# I2CADC.net
KiCad netlist of a schematic drawn in Altium Designer
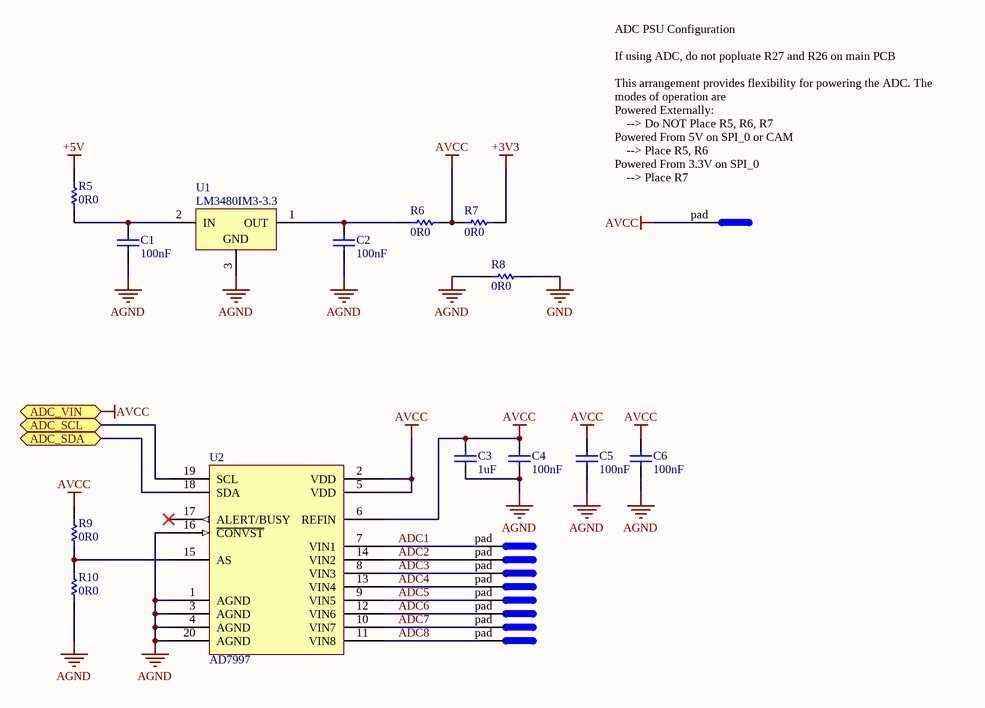
[diagram p0: I2CADC.SchDoc]

(export (version "E")
  (design (tool "Eeschema 10.0.6"))
  (components
    (comp (ref "A+")
      (value "~")
      (footprint "PAD_ROUND")
      (description "Pad")
      (libsource (lib "GRC sch library") (part "JP_pad"))
    )
    (comp (ref "A1")
      (value "~")
      (footprint "PAD_ROUND")
      (description "Pad")
      (libsource (lib "GRC sch library") (part "JP_pad"))
    )
    (comp (ref "A2")
      (value "~")
      (footprint "PAD_ROUND")
      (description "Pad")
      (libsource (lib "GRC sch library") (part "JP_pad"))
    )
    (comp (ref "A3")
      (value "~")
      (footprint "PAD_ROUND")
      (description "Pad")
      (libsource (lib "GRC sch library") (part "JP_pad"))
    )
    (comp (ref "A4")
      (value "~")
      (footprint "PAD_ROUND")
      (description "Pad")
      (libsource (lib "GRC sch library") (part "JP_pad"))
    )
    (comp (ref "A5")
      (value "~")
      (footprint "PAD_ROUND")
      (description "Pad")
      (libsource (lib "GRC sch library") (part "JP_pad"))
    )
    (comp (ref "A6")
      (value "~")
      (footprint "PAD_ROUND")
      (description "Pad")
      (libsource (lib "GRC sch library") (part "JP_pad"))
    )
    (comp (ref "A7")
      (value "~")
      (footprint "PAD_ROUND")
      (description "Pad")
      (libsource (lib "GRC sch library") (part "JP_pad"))
    )
    (comp (ref "A8")
      (value "~")
      (footprint "PAD_ROUND")
      (description "Pad")
      (libsource (lib "GRC sch library") (part "JP_pad"))
    )
    (comp (ref "C1")
      (value "100nF")
      (footprint "GRC PCB library:0603")
      (description "CAP CER .10UF 50V X5R 0603")
      (fields (field (name "MANUFACTURER") "Taiyo Yuden"))
      (libsource (lib "GRC sch library") (part "CP_100nF 0603"))
    )
    (comp (ref "C2")
      (value "100nF")
      (footprint "GRC PCB library:0603")
      (description "CAP CER .10UF 50V X5R 0603")
      (fields (field (name "MANUFACTURER") "Taiyo Yuden"))
      (libsource (lib "GRC sch library") (part "CP_100nF 0603"))
    )
    (comp (ref "C3")
      (value "1uF")
      (footprint "GRC PCB library:0603")
      (description "CAP CER 1.0UF 50V X5S 0603")
      (fields (field (name "MANUFACTURER") "Taiyo Yuden"))
      (libsource (lib "GRC sch library") (part "CP_1uF 0603"))
    )
    (comp (ref "C4")
      (value "100nF")
      (footprint "GRC PCB library:0603")
      (description "CAP CER .10UF 50V X5R 0603")
      (fields (field (name "MANUFACTURER") "Taiyo Yuden"))
      (libsource (lib "GRC sch library") (part "CP_100nF 0603"))
    )
    (comp (ref "C5")
      (value "100nF")
      (footprint "GRC PCB library:0603")
      (description "CAP CER .10UF 50V X5R 0603")
      (fields (field (name "MANUFACTURER") "Taiyo Yuden"))
      (libsource (lib "GRC sch library") (part "CP_100nF 0603"))
    )
    (comp (ref "C6")
      (value "100nF")
      (footprint "GRC PCB library:0603")
      (description "CAP CER .10UF 50V X5R 0603")
      (fields (field (name "MANUFACTURER") "Taiyo Yuden"))
      (libsource (lib "GRC sch library") (part "CP_100nF 0603"))
    )
    (comp (ref "R5")
      (value "0R0")
      (footprint "0805")
      (description "RES 0.0 OHM 1/10W 5% 1206 SMD")
      (fields (field (name "MANUFACTURER") "Rohm"))
      (libsource (lib "GRC sch library") (part "RS_0R0 0603"))
    )
    (comp (ref "R6")
      (value "0R0")
      (footprint "0805")
      (description "RES 0.0 OHM 1/10W 5% 1206 SMD")
      (fields (field (name "MANUFACTURER") "Rohm"))
      (libsource (lib "GRC sch library") (part "RS_0R0 0603"))
    )
    (comp (ref "R7")
      (value "0R0")
      (footprint "0805")
      (description "RES 0.0 OHM 1/10W 5% 1206 SMD")
      (fields (field (name "MANUFACTURER") "Rohm"))
      (libsource (lib "GRC sch library") (part "RS_0R0 0603"))
    )
    (comp (ref "R8")
      (value "0R0")
      (footprint "0805")
      (description "RES 0.0 OHM 1/10W 5% 1206 SMD")
      (fields (field (name "MANUFACTURER") "Rohm"))
      (libsource (lib "GRC sch library") (part "RS_0R0 0603"))
    )
    (comp (ref "R9")
      (value "0R0")
      (footprint "0805")
      (description "RES 0.0 OHM 1/10W 5% 0603 SMD")
      (fields (field (name "MANUFACTURER") "Rohm"))
      (libsource (lib "GRC sch library") (part "RS_0R0 0603"))
    )
    (comp (ref "R10")
      (value "0R0")
      (footprint "0805")
      (description "RES 0.0 OHM 1/10W 5% 0603 SMD")
      (fields (field (name "MANUFACTURER") "Rohm"))
      (libsource (lib "GRC sch library") (part "RS_0R0 0603"))
    )
    (comp (ref "U1")
      (value "LM3480IM3-3.3")
      (footprint "MF03A_N")
      (description "100 mA, SOT-23, Quasi Low-Dropout Linear Voltage Regulator")
      (fields
        (field (name "MANUFACTURER") "National Semiconductor")
        (field (name "DIGIKEYPARTNUMBER") "LM3480IM3-3.3CT-ND")
        (field (name "PUBLISHER") "Altium Limited")
      )
      (libsource (lib "NSC LDO") (part "LM3480IM3-3.3"))
    )
    (comp (ref "U2")
      (value "AD7997")
      (footprint "TSOP65P640-20AM")
      (description "10-bit 8 channel ADC")
      (libsource (lib "GRC sch library") (part "IC_AD7997"))
    )
  )
  (nets
    (net (code "1") (name "+3V3") (class "Default")
      (node (ref "R7") (pin "1") (pinfunction "1_1") (pintype "passive"))
    )
    (net (code "2") (name "+5V") (class "Default")
      (node (ref "R5") (pin "2") (pinfunction "2_2") (pintype "passive"))
    )
    (net (code "3") (name "/ADC1") (class "Default")
      (node (ref "A1") (pin "pad") (pintype "passive"))
      (node (ref "U2") (pin "7") (pinfunction "VIN1_7") (pintype "passive"))
    )
    (net (code "4") (name "/ADC2") (class "Default")
      (node (ref "A2") (pin "pad") (pintype "passive"))
      (node (ref "U2") (pin "14") (pinfunction "VIN2_14") (pintype "passive"))
    )
    (net (code "5") (name "/ADC3") (class "Default")
      (node (ref "A3") (pin "pad") (pintype "passive"))
      (node (ref "U2") (pin "8") (pinfunction "VIN3_8") (pintype "passive"))
    )
    (net (code "6") (name "/ADC4") (class "Default")
      (node (ref "A4") (pin "pad") (pintype "passive"))
      (node (ref "U2") (pin "13") (pinfunction "VIN4_13") (pintype "passive"))
    )
    (net (code "7") (name "/ADC5") (class "Default")
      (node (ref "A5") (pin "pad") (pintype "passive"))
      (node (ref "U2") (pin "9") (pinfunction "VIN5_9") (pintype "passive"))
    )
    (net (code "8") (name "/ADC6") (class "Default")
      (node (ref "A6") (pin "pad") (pintype "passive"))
      (node (ref "U2") (pin "12") (pinfunction "VIN6_12") (pintype "passive"))
    )
    (net (code "9") (name "/ADC7") (class "Default")
      (node (ref "A7") (pin "pad") (pintype "passive"))
      (node (ref "U2") (pin "10") (pinfunction "VIN7_10") (pintype "passive"))
    )
    (net (code "10") (name "/ADC8") (class "Default")
      (node (ref "A8") (pin "pad") (pintype "passive"))
      (node (ref "U2") (pin "11") (pinfunction "VIN8_11") (pintype "passive"))
    )
    (net (code "11") (name "/ADC_SCL") (class "Default")
      (node (ref "U2") (pin "19") (pinfunction "SCL_19") (pintype "passive"))
    )
    (net (code "12") (name "/ADC_SDA") (class "Default")
      (node (ref "U2") (pin "18") (pinfunction "SDA_18") (pintype "passive"))
    )
    (net (code "13") (name "AGND") (class "Default")
      (node (ref "C1") (pin "1") (pinfunction "1_1") (pintype "passive"))
      (node (ref "C2") (pin "1") (pinfunction "1_1") (pintype "passive"))
      (node (ref "C3") (pin "1") (pinfunction "1_1") (pintype "passive"))
      (node (ref "C4") (pin "1") (pinfunction "1_1") (pintype "passive"))
      (node (ref "C5") (pin "1") (pinfunction "1_1") (pintype "passive"))
      (node (ref "C6") (pin "1") (pinfunction "1_1") (pintype "passive"))
      (node (ref "R10") (pin "2") (pinfunction "2_2") (pintype "passive"))
      (node (ref "R8") (pin "1") (pinfunction "1_1") (pintype "passive"))
      (node (ref "U1") (pin "3") (pinfunction "GND_3") (pintype "power_in"))
      (node (ref "U2") (pin "1") (pinfunction "AGND_1") (pintype "power_in"))
      (node (ref "U2") (pin "16") (pinfunction "~{CONVST}_16") (pintype "input"))
      (node (ref "U2") (pin "20") (pinfunction "AGND_20") (pintype "power_in"))
      (node (ref "U2") (pin "3") (pinfunction "AGND_3") (pintype "power_in"))
      (node (ref "U2") (pin "4") (pinfunction "AGND_4") (pintype "power_in"))
    )
    (net (code "14") (name "AVCC") (class "Default")
      (node (ref "A+") (pin "pad") (pintype "passive"))
      (node (ref "C3") (pin "2") (pinfunction "2_2") (pintype "passive"))
      (node (ref "C4") (pin "2") (pinfunction "2_2") (pintype "passive"))
      (node (ref "C5") (pin "2") (pinfunction "2_2") (pintype "passive"))
      (node (ref "C6") (pin "2") (pinfunction "2_2") (pintype "passive"))
      (node (ref "R6") (pin "1") (pinfunction "1_1") (pintype "passive"))
      (node (ref "R7") (pin "2") (pinfunction "2_2") (pintype "passive"))
      (node (ref "R9") (pin "2") (pinfunction "2_2") (pintype "passive"))
      (node (ref "U2") (pin "2") (pinfunction "VDD_2") (pintype "power_in"))
      (node (ref "U2") (pin "5") (pinfunction "VDD_5") (pintype "power_in"))
      (node (ref "U2") (pin "6") (pinfunction "REFIN_6") (pintype "passive"))
    )
    (net (code "15") (name "GND") (class "Default")
      (node (ref "R8") (pin "2") (pinfunction "2_2") (pintype "passive"))
    )
    (net (code "16") (name "Net-(U1-IN)") (class "Default")
      (node (ref "C1") (pin "2") (pinfunction "2_2") (pintype "passive"))
      (node (ref "R5") (pin "1") (pinfunction "1_1") (pintype "passive"))
      (node (ref "U1") (pin "2") (pinfunction "IN_2") (pintype "power_in"))
    )
    (net (code "17") (name "Net-(U1-OUT)") (class "Default")
      (node (ref "C2") (pin "2") (pinfunction "2_2") (pintype "passive"))
      (node (ref "R6") (pin "2") (pinfunction "2_2") (pintype "passive"))
      (node (ref "U1") (pin "1") (pinfunction "OUT_1") (pintype "power_in"))
    )
    (net (code "18") (name "Net-(U2-AS)") (class "Default")
      (node (ref "R10") (pin "1") (pinfunction "1_1") (pintype "passive"))
      (node (ref "R9") (pin "1") (pinfunction "1_1") (pintype "passive"))
      (node (ref "U2") (pin "15") (pinfunction "AS_15") (pintype "tri_state"))
    )
    (net (code "19") (name "unconnected-(U2-ALERT{slash}BUSY-Pad17)") (class "Default")
      (node (ref "U2") (pin "17") (pinfunction "ALERT/BUSY_17") (pintype "output+no_connect"))
    )
  )
)
